# Preamp1_schematic.net
KiCad netlist of a schematic drawn in Altium Designer
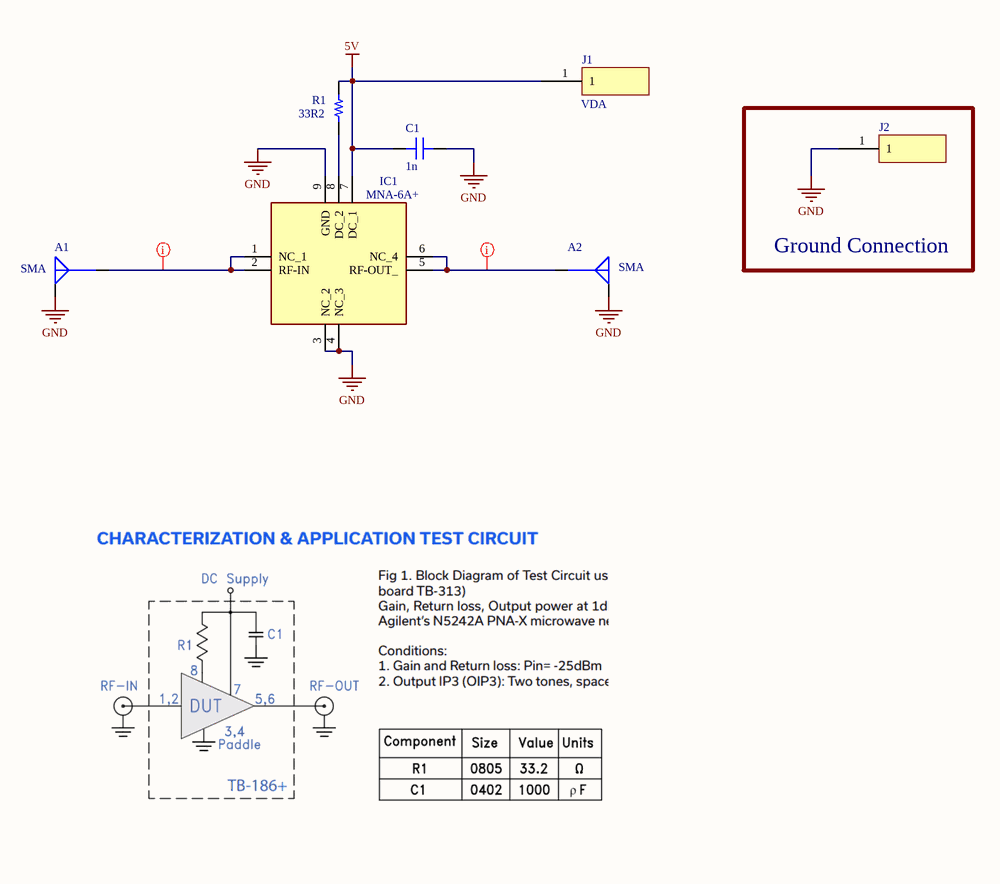
[diagram p0: Preamp1_schematic.SchDoc]

(export (version "E")
  (design (tool "Eeschema 10.0.6"))
  (components
    (comp (ref "A1")
      (value "0732511150")
      (footprint "MOLEX SD-73251-115")
      (description "CONN SMA RCPT STR 50OHM EDGE MNT")
      (fields (field (name "CONNECTOR STYLE") "SMA") (field (name "MANUFACTURER") "Molex"))
      (libsource (lib "Celestial Altium Library - altium_library") (part "Basic Antenna"))
    )
    (comp (ref "A2")
      (value "0732511150")
      (footprint "MOLEX SD-73251-115")
      (description "CONN SMA RCPT STR 50OHM EDGE MNT")
      (fields (field (name "CONNECTOR STYLE") "SMA") (field (name "MANUFACTURER") "Molex"))
      (libsource (lib "Celestial Altium Library - altium_library") (part "Basic Antenna"))
    )
    (comp (ref "C1")
      (value "1n")
      (footprint "CAP 0603_1608 RF")
      (description "CAP CER 1000PF 50V 0603")
      (fields (field (name "PART NUMBER") "UMK107SD102JA-T") (field (name "MANUFACTURER") "Taiyo Yuden"))
      (libsource (lib "Celestial Altium Library - altium_library") (part "Capacitor"))
    )
    (comp (ref "IC1")
      (value "MNA-6A+")
      (footprint "SamacSys:MNA6A")
      (description "Integrated Circuit")
      (fields (field (name "MOUSER PART NUMBER") "139-MNA-6A"))
      (libsource (lib "*") (part "MNA-6A+"))
    )
    (comp (ref "J1")
      (value "Nail_Head")
      (footprint "Nail_Head")
      (description "1460-2-00-80-00-00-03-0 Mill-Max")
      (libsource (lib "ARIS_COM_Transponder") (part "Nail_Head"))
    )
    (comp (ref "J2")
      (value "Nail_Head")
      (footprint "Nail_Head")
      (description "1460-2-00-80-00-00-03-0 Mill-Max")
      (libsource (lib "ARIS_COM_Transponder") (part "Nail_Head"))
    )
    (comp (ref "R1")
      (value "33R2")
      (footprint "RES 0805_2012")
      (description "RES SMD 33.2 OHM 1% 1/2W 0805")
      (fields (field (name "PART NUMBER") "RCS080533R2FKEA") (field (name "MANUFACTURER") "Vishay Dale"))
      (libsource (lib "Celestial Altium Library - altium_library") (part "Resistor"))
    )
  )
  (nets
    (net (code "1") (name "5V") (class "Default")
      (node (ref "C1") (pin "1") (pinfunction "1_1") (pintype "passive"))
      (node (ref "IC1") (pin "7") (pinfunction "DC_1_7") (pintype "passive"))
      (node (ref "J1") (pin "1") (pinfunction "1_1") (pintype "passive"))
      (node (ref "R1") (pin "2") (pinfunction "2_2") (pintype "passive"))
    )
    (net (code "2") (name "GND") (class "Default")
      (node (ref "A1") (pin "G") (pinfunction "G_G") (pintype "passive"))
      (node (ref "A2") (pin "G") (pinfunction "G_G") (pintype "passive"))
      (node (ref "C1") (pin "2") (pinfunction "2_2") (pintype "passive"))
      (node (ref "IC1") (pin "3") (pinfunction "NC_2_3") (pintype "passive"))
      (node (ref "IC1") (pin "4") (pinfunction "NC_3_4") (pintype "passive"))
      (node (ref "IC1") (pin "9") (pinfunction "GND_9") (pintype "passive"))
      (node (ref "J2") (pin "1") (pinfunction "1_1") (pintype "passive"))
    )
    (net (code "3") (name "Net-(IC1-DC_2)") (class "Default")
      (node (ref "IC1") (pin "8") (pinfunction "DC_2_8") (pintype "passive"))
      (node (ref "R1") (pin "1") (pinfunction "1_1") (pintype "passive"))
    )
    (net (code "4") (name "Net-(IC1-NC_1)") (class "Default")
      (node (ref "A1") (pin "S") (pinfunction "S_S") (pintype "passive"))
      (node (ref "IC1") (pin "1") (pinfunction "NC_1_1") (pintype "passive"))
      (node (ref "IC1") (pin "2") (pinfunction "RF-IN_2") (pintype "passive"))
    )
    (net (code "5") (name "Net-(IC1-NC_4)") (class "Default")
      (node (ref "A2") (pin "S") (pinfunction "S_S") (pintype "passive"))
      (node (ref "IC1") (pin "5") (pinfunction "RF-OUT__5") (pintype "passive"))
      (node (ref "IC1") (pin "6") (pinfunction "NC_4_6") (pintype "passive"))
    )
  )
)
